# RasPi_adapt.net
KiCad netlist of a schematic drawn in EAGLE
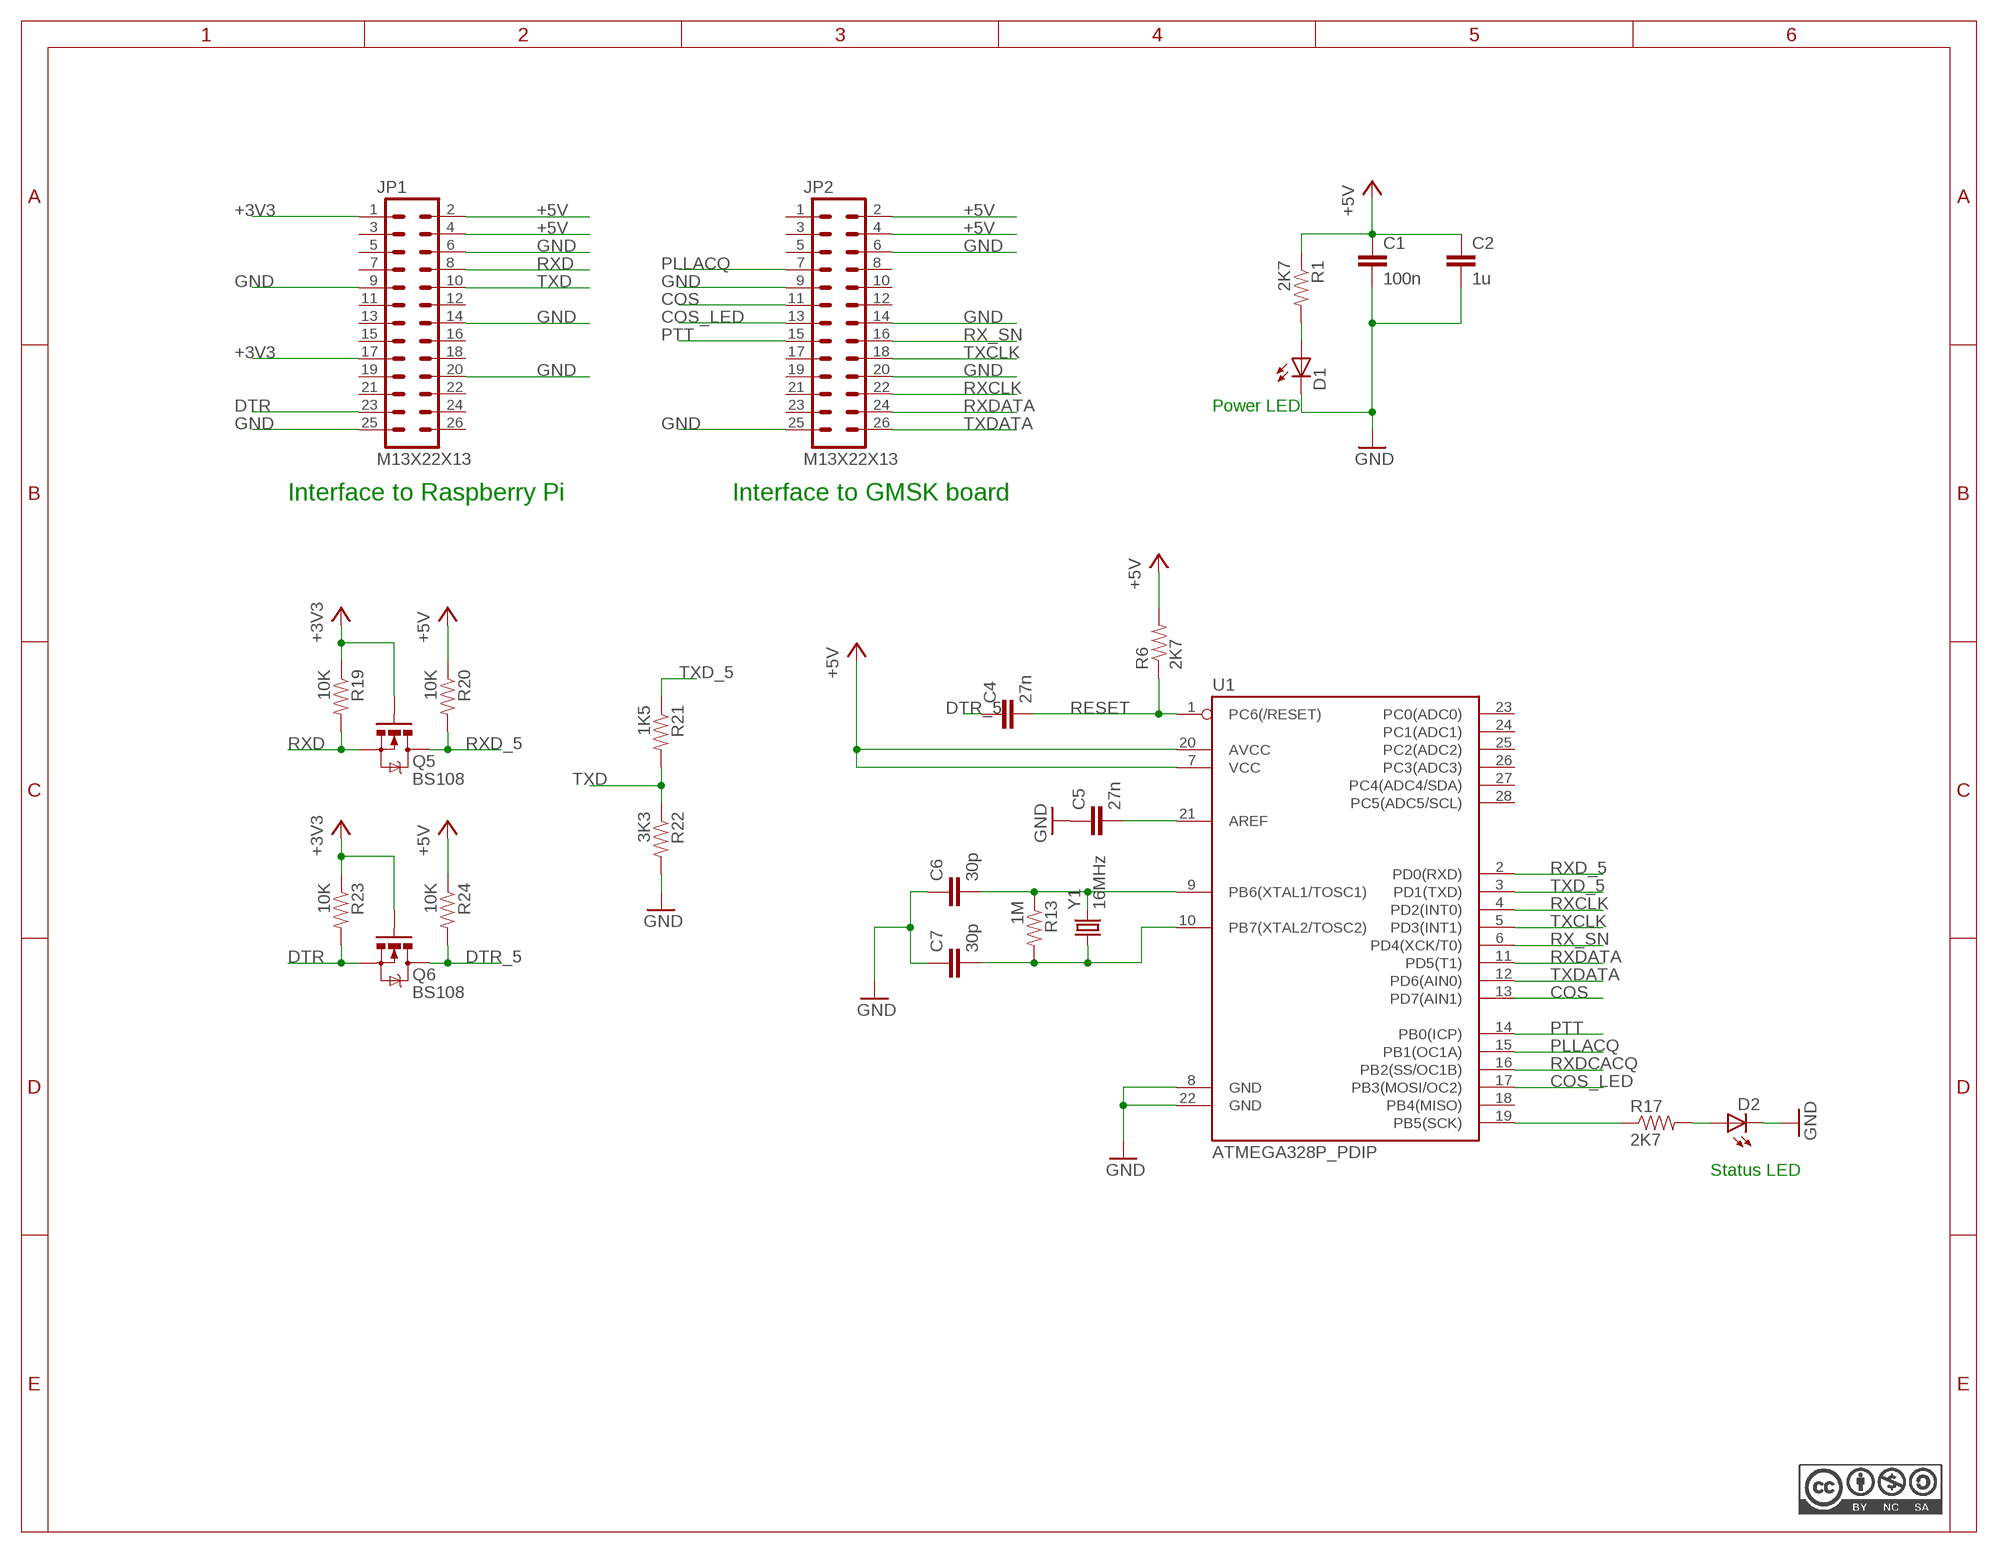
[diagram p0: schematic, sheet 1]

(export (version "E")
  (design (tool "Eeschema 10.0.6"))
  (components
    (comp (ref "C1")
      (value "100n")
      (footprint "eagle-import:CAP-PTH-SMALLEZ")
      (libsource (lib "eagle-import") (part "CAPEZ"))
    )
    (comp (ref "C2")
      (value "1u")
      (footprint "eagle-import:CAP-PTH-SMALLEZ")
      (libsource (lib "eagle-import") (part "CAPEZ"))
    )
    (comp (ref "C4")
      (value "27n")
      (footprint "eagle-import:CAP-PTH-SMALLEZ")
      (libsource (lib "eagle-import") (part "CAPEZ"))
    )
    (comp (ref "C5")
      (value "27n")
      (footprint "eagle-import:CAP-PTH-SMALLEZ")
      (libsource (lib "eagle-import") (part "CAPEZ"))
    )
    (comp (ref "C6")
      (value "30p")
      (footprint "eagle-import:CAP-PTH-SMALLEZ")
      (libsource (lib "eagle-import") (part "CAPEZ"))
    )
    (comp (ref "C7")
      (value "30p")
      (footprint "eagle-import:CAP-PTH-SMALLEZ")
      (libsource (lib "eagle-import") (part "CAPEZ"))
    )
    (comp (ref "D1")
      (value "LED3MM")
      (footprint "eagle-import:LED3MM")
      (libsource (lib "eagle-import") (part "LED3MM"))
    )
    (comp (ref "D2")
      (value "LED3MM")
      (footprint "eagle-import:LED3MM")
      (libsource (lib "eagle-import") (part "LED3MM"))
    )
    (comp (ref "JP1")
      (value "M13X22X13")
      (footprint "eagle-import:2X13")
      (libsource (lib "eagle-import") (part "M13X22X13"))
    )
    (comp (ref "JP2")
      (value "M13X22X13")
      (footprint "eagle-import:2X13")
      (libsource (lib "eagle-import") (part "M13X22X13"))
    )
    (comp (ref "Q5")
      (value "BS108")
      (footprint "eagle-import:TO-92")
      (libsource (lib "eagle-import") (part "MOSFET-NCHANNELBS170"))
    )
    (comp (ref "Q6")
      (value "BS108")
      (footprint "eagle-import:TO-92")
      (libsource (lib "eagle-import") (part "MOSFET-NCHANNELBS170"))
    )
    (comp (ref "R1")
      (value "2K7")
      (footprint "eagle-import:AXIAL-0.3EZ")
      (libsource (lib "eagle-import") (part "RESISTOREZ"))
    )
    (comp (ref "R6")
      (value "2K7")
      (footprint "eagle-import:AXIAL-0.3EZ")
      (libsource (lib "eagle-import") (part "RESISTOREZ"))
    )
    (comp (ref "R13")
      (value "1M")
      (footprint "eagle-import:AXIAL-0.3EZ")
      (libsource (lib "eagle-import") (part "RESISTOREZ"))
    )
    (comp (ref "R17")
      (value "2K7")
      (footprint "eagle-import:AXIAL-0.3EZ")
      (libsource (lib "eagle-import") (part "RESISTOREZ"))
    )
    (comp (ref "R19")
      (value "10K")
      (footprint "eagle-import:AXIAL-0.3EZ")
      (libsource (lib "eagle-import") (part "RESISTOREZ"))
    )
    (comp (ref "R20")
      (value "10K")
      (footprint "eagle-import:AXIAL-0.3EZ")
      (libsource (lib "eagle-import") (part "RESISTOREZ"))
    )
    (comp (ref "R21")
      (value "1K5")
      (footprint "eagle-import:AXIAL-0.3EZ")
      (libsource (lib "eagle-import") (part "RESISTOREZ"))
    )
    (comp (ref "R22")
      (value "3K3")
      (footprint "eagle-import:AXIAL-0.3EZ")
      (libsource (lib "eagle-import") (part "RESISTOREZ"))
    )
    (comp (ref "R23")
      (value "10K")
      (footprint "eagle-import:AXIAL-0.3EZ")
      (libsource (lib "eagle-import") (part "RESISTOREZ"))
    )
    (comp (ref "R24")
      (value "10K")
      (footprint "eagle-import:AXIAL-0.3EZ")
      (libsource (lib "eagle-import") (part "RESISTOREZ"))
    )
    (comp (ref "U1")
      (value "ATMEGA328P_PDIP")
      (footprint "eagle-import:DIL28-3")
      (libsource (lib "eagle-import") (part "ATMEGA328P_PDIP"))
    )
    (comp (ref "Y1")
      (value "16MHz")
      (footprint "eagle-import:CRYSTAL_HC49_S")
      (libsource (lib "eagle-import") (part "CRYSTAL_CRYSTALHC49S"))
    )
  )
  (nets
    (net (code "1") (name "+3V3") (class "Default")
      (node (ref "JP1") (pin "1") (pinfunction "1_1") (pintype "passive"))
      (node (ref "JP1") (pin "17") (pinfunction "17_17") (pintype "passive"))
      (node (ref "Q5") (pin "2") (pinfunction "G_2") (pintype "passive"))
      (node (ref "Q6") (pin "2") (pinfunction "G_2") (pintype "passive"))
      (node (ref "R19") (pin "P$1") (pinfunction "1_P$1") (pintype "passive"))
      (node (ref "R23") (pin "P$1") (pinfunction "1_P$1") (pintype "passive"))
    )
    (net (code "2") (name "+5V") (class "Default")
      (node (ref "C1") (pin "1") (pinfunction "1_1") (pintype "passive"))
      (node (ref "C2") (pin "1") (pinfunction "1_1") (pintype "passive"))
      (node (ref "JP1") (pin "2") (pinfunction "2_2") (pintype "passive"))
      (node (ref "JP1") (pin "4") (pinfunction "4_4") (pintype "passive"))
      (node (ref "JP2") (pin "2") (pinfunction "2_2") (pintype "passive"))
      (node (ref "JP2") (pin "4") (pinfunction "4_4") (pintype "passive"))
      (node (ref "R1") (pin "P$1") (pinfunction "1_P$1") (pintype "passive"))
      (node (ref "R20") (pin "P$1") (pinfunction "1_P$1") (pintype "passive"))
      (node (ref "R24") (pin "P$1") (pinfunction "1_P$1") (pintype "passive"))
      (node (ref "R6") (pin "P$2") (pinfunction "2_P$2") (pintype "passive"))
      (node (ref "U1") (pin "20") (pinfunction "AVCC_20") (pintype "bidirectional"))
      (node (ref "U1") (pin "7") (pinfunction "VCC_7") (pintype "bidirectional"))
    )
    (net (code "3") (name "/COS") (class "Default")
      (node (ref "JP2") (pin "11") (pinfunction "11_11") (pintype "passive"))
      (node (ref "U1") (pin "13") (pinfunction "PD7(AIN1)_13") (pintype "bidirectional"))
    )
    (net (code "4") (name "/COS_LED") (class "Default")
      (node (ref "JP2") (pin "13") (pinfunction "13_13") (pintype "passive"))
      (node (ref "U1") (pin "17") (pinfunction "PB3(MOSI/OC2)_17") (pintype "bidirectional"))
    )
    (net (code "5") (name "/DTR") (class "Default")
      (node (ref "JP1") (pin "23") (pinfunction "23_23") (pintype "passive"))
      (node (ref "Q6") (pin "3") (pinfunction "S_3") (pintype "passive"))
      (node (ref "R23") (pin "P$2") (pinfunction "2_P$2") (pintype "passive"))
    )
    (net (code "6") (name "/DTR_5") (class "Default")
      (node (ref "C4") (pin "1") (pinfunction "1_1") (pintype "passive"))
      (node (ref "Q6") (pin "1") (pinfunction "D_1") (pintype "passive"))
      (node (ref "R24") (pin "P$2") (pinfunction "2_P$2") (pintype "passive"))
    )
    (net (code "7") (name "/PLLACQ") (class "Default")
      (node (ref "JP2") (pin "7") (pinfunction "7_7") (pintype "passive"))
      (node (ref "U1") (pin "15") (pinfunction "PB1(OC1A)_15") (pintype "bidirectional"))
    )
    (net (code "8") (name "/PTT") (class "Default")
      (node (ref "JP2") (pin "15") (pinfunction "15_15") (pintype "passive"))
      (node (ref "U1") (pin "14") (pinfunction "PB0(ICP)_14") (pintype "bidirectional"))
    )
    (net (code "9") (name "/RESET") (class "Default")
      (node (ref "C4") (pin "2") (pinfunction "2_2") (pintype "passive"))
      (node (ref "R6") (pin "P$1") (pinfunction "1_P$1") (pintype "passive"))
      (node (ref "U1") (pin "1") (pinfunction "PC6(/RESET)_1") (pintype "bidirectional"))
    )
    (net (code "10") (name "/RXCLK") (class "Default")
      (node (ref "JP2") (pin "22") (pinfunction "22_22") (pintype "passive"))
      (node (ref "U1") (pin "4") (pinfunction "PD2(INT0)_4") (pintype "bidirectional"))
    )
    (net (code "11") (name "/RXD") (class "Default")
      (node (ref "JP1") (pin "8") (pinfunction "8_8") (pintype "passive"))
      (node (ref "Q5") (pin "3") (pinfunction "S_3") (pintype "passive"))
      (node (ref "R19") (pin "P$2") (pinfunction "2_P$2") (pintype "passive"))
    )
    (net (code "12") (name "/RXDATA") (class "Default")
      (node (ref "JP2") (pin "24") (pinfunction "24_24") (pintype "passive"))
      (node (ref "U1") (pin "11") (pinfunction "PD5(T1)_11") (pintype "bidirectional"))
    )
    (net (code "13") (name "/RXDCACQ") (class "Default")
      (node (ref "U1") (pin "16") (pinfunction "PB2(SS/OC1B)_16") (pintype "bidirectional"))
    )
    (net (code "14") (name "/RXD_5") (class "Default")
      (node (ref "Q5") (pin "1") (pinfunction "D_1") (pintype "passive"))
      (node (ref "R20") (pin "P$2") (pinfunction "2_P$2") (pintype "passive"))
      (node (ref "U1") (pin "2") (pinfunction "PD0(RXD)_2") (pintype "bidirectional"))
    )
    (net (code "15") (name "/RX_SN") (class "Default")
      (node (ref "JP2") (pin "16") (pinfunction "16_16") (pintype "passive"))
      (node (ref "U1") (pin "6") (pinfunction "PD4(XCK/T0)_6") (pintype "bidirectional"))
    )
    (net (code "16") (name "/TXCLK") (class "Default")
      (node (ref "JP2") (pin "18") (pinfunction "18_18") (pintype "passive"))
      (node (ref "U1") (pin "5") (pinfunction "PD3(INT1)_5") (pintype "bidirectional"))
    )
    (net (code "17") (name "/TXD") (class "Default")
      (node (ref "JP1") (pin "10") (pinfunction "10_10") (pintype "passive"))
      (node (ref "R21") (pin "P$2") (pinfunction "2_P$2") (pintype "passive"))
      (node (ref "R22") (pin "P$1") (pinfunction "1_P$1") (pintype "passive"))
    )
    (net (code "18") (name "/TXDATA") (class "Default")
      (node (ref "JP2") (pin "26") (pinfunction "26_26") (pintype "passive"))
      (node (ref "U1") (pin "12") (pinfunction "PD6(AIN0)_12") (pintype "bidirectional"))
    )
    (net (code "19") (name "/TXD_5") (class "Default")
      (node (ref "R21") (pin "P$1") (pinfunction "1_P$1") (pintype "passive"))
      (node (ref "U1") (pin "3") (pinfunction "PD1(TXD)_3") (pintype "bidirectional"))
    )
    (net (code "20") (name "GND") (class "Default")
      (node (ref "C1") (pin "2") (pinfunction "2_2") (pintype "passive"))
      (node (ref "C2") (pin "2") (pinfunction "2_2") (pintype "passive"))
      (node (ref "C5") (pin "1") (pinfunction "1_1") (pintype "passive"))
      (node (ref "C6") (pin "1") (pinfunction "1_1") (pintype "passive"))
      (node (ref "C7") (pin "1") (pinfunction "1_1") (pintype "passive"))
      (node (ref "D1") (pin "K") (pinfunction "C_K") (pintype "passive"))
      (node (ref "D2") (pin "K") (pinfunction "C_K") (pintype "passive"))
      (node (ref "JP1") (pin "14") (pinfunction "14_14") (pintype "passive"))
      (node (ref "JP1") (pin "20") (pinfunction "20_20") (pintype "passive"))
      (node (ref "JP1") (pin "25") (pinfunction "25_25") (pintype "passive"))
      (node (ref "JP1") (pin "6") (pinfunction "6_6") (pintype "passive"))
      (node (ref "JP1") (pin "9") (pinfunction "9_9") (pintype "passive"))
      (node (ref "JP2") (pin "14") (pinfunction "14_14") (pintype "passive"))
      (node (ref "JP2") (pin "20") (pinfunction "20_20") (pintype "passive"))
      (node (ref "JP2") (pin "25") (pinfunction "25_25") (pintype "passive"))
      (node (ref "JP2") (pin "6") (pinfunction "6_6") (pintype "passive"))
      (node (ref "JP2") (pin "9") (pinfunction "9_9") (pintype "passive"))
      (node (ref "R22") (pin "P$2") (pinfunction "2_P$2") (pintype "passive"))
      (node (ref "U1") (pin "22") (pinfunction "GND_22") (pintype "bidirectional"))
      (node (ref "U1") (pin "8") (pinfunction "GND_8") (pintype "bidirectional"))
    )
    (net (code "21") (name "Net-(R1-2)") (class "Default")
      (node (ref "D1") (pin "A") (pinfunction "A_A") (pintype "passive"))
      (node (ref "R1") (pin "P$2") (pinfunction "2_P$2") (pintype "passive"))
    )
    (net (code "22") (name "Net-(R13-1)") (class "Default")
      (node (ref "C6") (pin "2") (pinfunction "2_2") (pintype "passive"))
      (node (ref "R13") (pin "P$1") (pinfunction "1_P$1") (pintype "passive"))
      (node (ref "U1") (pin "9") (pinfunction "PB6(XTAL1/TOSC1)_9") (pintype "bidirectional"))
      (node (ref "Y1") (pin "2") (pinfunction "2_2") (pintype "passive"))
    )
    (net (code "23") (name "Net-(R13-2)") (class "Default")
      (node (ref "C7") (pin "2") (pinfunction "2_2") (pintype "passive"))
      (node (ref "R13") (pin "P$2") (pinfunction "2_P$2") (pintype "passive"))
      (node (ref "U1") (pin "10") (pinfunction "PB7(XTAL2/TOSC2)_10") (pintype "bidirectional"))
      (node (ref "Y1") (pin "1") (pinfunction "1_1") (pintype "passive"))
    )
    (net (code "24") (name "Net-(R17-1)") (class "Default")
      (node (ref "R17") (pin "P$1") (pinfunction "1_P$1") (pintype "passive"))
      (node (ref "U1") (pin "19") (pinfunction "PB5(SCK)_19") (pintype "bidirectional"))
    )
    (net (code "25") (name "Net-(R17-2)") (class "Default")
      (node (ref "D2") (pin "A") (pinfunction "A_A") (pintype "passive"))
      (node (ref "R17") (pin "P$2") (pinfunction "2_P$2") (pintype "passive"))
    )
    (net (code "26") (name "Net-(U1-AREF)") (class "Default")
      (node (ref "C5") (pin "2") (pinfunction "2_2") (pintype "passive"))
      (node (ref "U1") (pin "21") (pinfunction "AREF_21") (pintype "bidirectional"))
    )
    (net (code "27") (name "unconnected-(JP1-Pad3)") (class "Default")
      (node (ref "JP1") (pin "3") (pinfunction "3_3") (pintype "passive"))
    )
    (net (code "28") (name "unconnected-(JP1-Pad5)") (class "Default")
      (node (ref "JP1") (pin "5") (pinfunction "5_5") (pintype "passive"))
    )
    (net (code "29") (name "unconnected-(JP1-Pad7)") (class "Default")
      (node (ref "JP1") (pin "7") (pinfunction "7_7") (pintype "passive"))
    )
    (net (code "30") (name "unconnected-(JP1-Pad11)") (class "Default")
      (node (ref "JP1") (pin "11") (pinfunction "11_11") (pintype "passive"))
    )
    (net (code "31") (name "unconnected-(JP1-Pad12)") (class "Default")
      (node (ref "JP1") (pin "12") (pinfunction "12_12") (pintype "passive"))
    )
    (net (code "32") (name "unconnected-(JP1-Pad13)") (class "Default")
      (node (ref "JP1") (pin "13") (pinfunction "13_13") (pintype "passive"))
    )
    (net (code "33") (name "unconnected-(JP1-Pad15)") (class "Default")
      (node (ref "JP1") (pin "15") (pinfunction "15_15") (pintype "passive"))
    )
    (net (code "34") (name "unconnected-(JP1-Pad16)") (class "Default")
      (node (ref "JP1") (pin "16") (pinfunction "16_16") (pintype "passive"))
    )
    (net (code "35") (name "unconnected-(JP1-Pad18)") (class "Default")
      (node (ref "JP1") (pin "18") (pinfunction "18_18") (pintype "passive"))
    )
    (net (code "36") (name "unconnected-(JP1-Pad19)") (class "Default")
      (node (ref "JP1") (pin "19") (pinfunction "19_19") (pintype "passive"))
    )
    (net (code "37") (name "unconnected-(JP1-Pad21)") (class "Default")
      (node (ref "JP1") (pin "21") (pinfunction "21_21") (pintype "passive"))
    )
    (net (code "38") (name "unconnected-(JP1-Pad22)") (class "Default")
      (node (ref "JP1") (pin "22") (pinfunction "22_22") (pintype "passive"))
    )
    (net (code "39") (name "unconnected-(JP1-Pad24)") (class "Default")
      (node (ref "JP1") (pin "24") (pinfunction "24_24") (pintype "passive"))
    )
    (net (code "40") (name "unconnected-(JP1-Pad26)") (class "Default")
      (node (ref "JP1") (pin "26") (pinfunction "26_26") (pintype "passive"))
    )
    (net (code "41") (name "unconnected-(JP2-Pad1)") (class "Default")
      (node (ref "JP2") (pin "1") (pinfunction "1_1") (pintype "passive"))
    )
    (net (code "42") (name "unconnected-(JP2-Pad3)") (class "Default")
      (node (ref "JP2") (pin "3") (pinfunction "3_3") (pintype "passive"))
    )
    (net (code "43") (name "unconnected-(JP2-Pad5)") (class "Default")
      (node (ref "JP2") (pin "5") (pinfunction "5_5") (pintype "passive"))
    )
    (net (code "44") (name "unconnected-(JP2-Pad8)") (class "Default")
      (node (ref "JP2") (pin "8") (pinfunction "8_8") (pintype "passive"))
    )
    (net (code "45") (name "unconnected-(JP2-Pad10)") (class "Default")
      (node (ref "JP2") (pin "10") (pinfunction "10_10") (pintype "passive"))
    )
    (net (code "46") (name "unconnected-(JP2-Pad12)") (class "Default")
      (node (ref "JP2") (pin "12") (pinfunction "12_12") (pintype "passive"))
    )
    (net (code "47") (name "unconnected-(JP2-Pad17)") (class "Default")
      (node (ref "JP2") (pin "17") (pinfunction "17_17") (pintype "passive"))
    )
    (net (code "48") (name "unconnected-(JP2-Pad19)") (class "Default")
      (node (ref "JP2") (pin "19") (pinfunction "19_19") (pintype "passive"))
    )
    (net (code "49") (name "unconnected-(JP2-Pad21)") (class "Default")
      (node (ref "JP2") (pin "21") (pinfunction "21_21") (pintype "passive"))
    )
    (net (code "50") (name "unconnected-(JP2-Pad23)") (class "Default")
      (node (ref "JP2") (pin "23") (pinfunction "23_23") (pintype "passive"))
    )
    (net (code "51") (name "unconnected-(U1-PB4(MISO)-Pad18)") (class "Default")
      (node (ref "U1") (pin "18") (pinfunction "PB4(MISO)_18") (pintype "bidirectional"))
    )
    (net (code "52") (name "unconnected-(U1-PC0(ADC0)-Pad23)") (class "Default")
      (node (ref "U1") (pin "23") (pinfunction "PC0(ADC0)_23") (pintype "bidirectional"))
    )
    (net (code "53") (name "unconnected-(U1-PC1(ADC1)-Pad24)") (class "Default")
      (node (ref "U1") (pin "24") (pinfunction "PC1(ADC1)_24") (pintype "bidirectional"))
    )
    (net (code "54") (name "unconnected-(U1-PC2(ADC2)-Pad25)") (class "Default")
      (node (ref "U1") (pin "25") (pinfunction "PC2(ADC2)_25") (pintype "bidirectional"))
    )
    (net (code "55") (name "unconnected-(U1-PC3(ADC3)-Pad26)") (class "Default")
      (node (ref "U1") (pin "26") (pinfunction "PC3(ADC3)_26") (pintype "bidirectional"))
    )
    (net (code "56") (name "unconnected-(U1-PC4(ADC4{slash}SDA)-Pad27)") (class "Default")
      (node (ref "U1") (pin "27") (pinfunction "PC4(ADC4/SDA)_27") (pintype "bidirectional"))
    )
    (net (code "57") (name "unconnected-(U1-PC5(ADC5{slash}SCL)-Pad28)") (class "Default")
      (node (ref "U1") (pin "28") (pinfunction "PC5(ADC5/SCL)_28") (pintype "bidirectional"))
    )
  )
)
